# 7_dc_dc_5v_payloads.net
KiCad netlist of a schematic drawn in Altium Designer
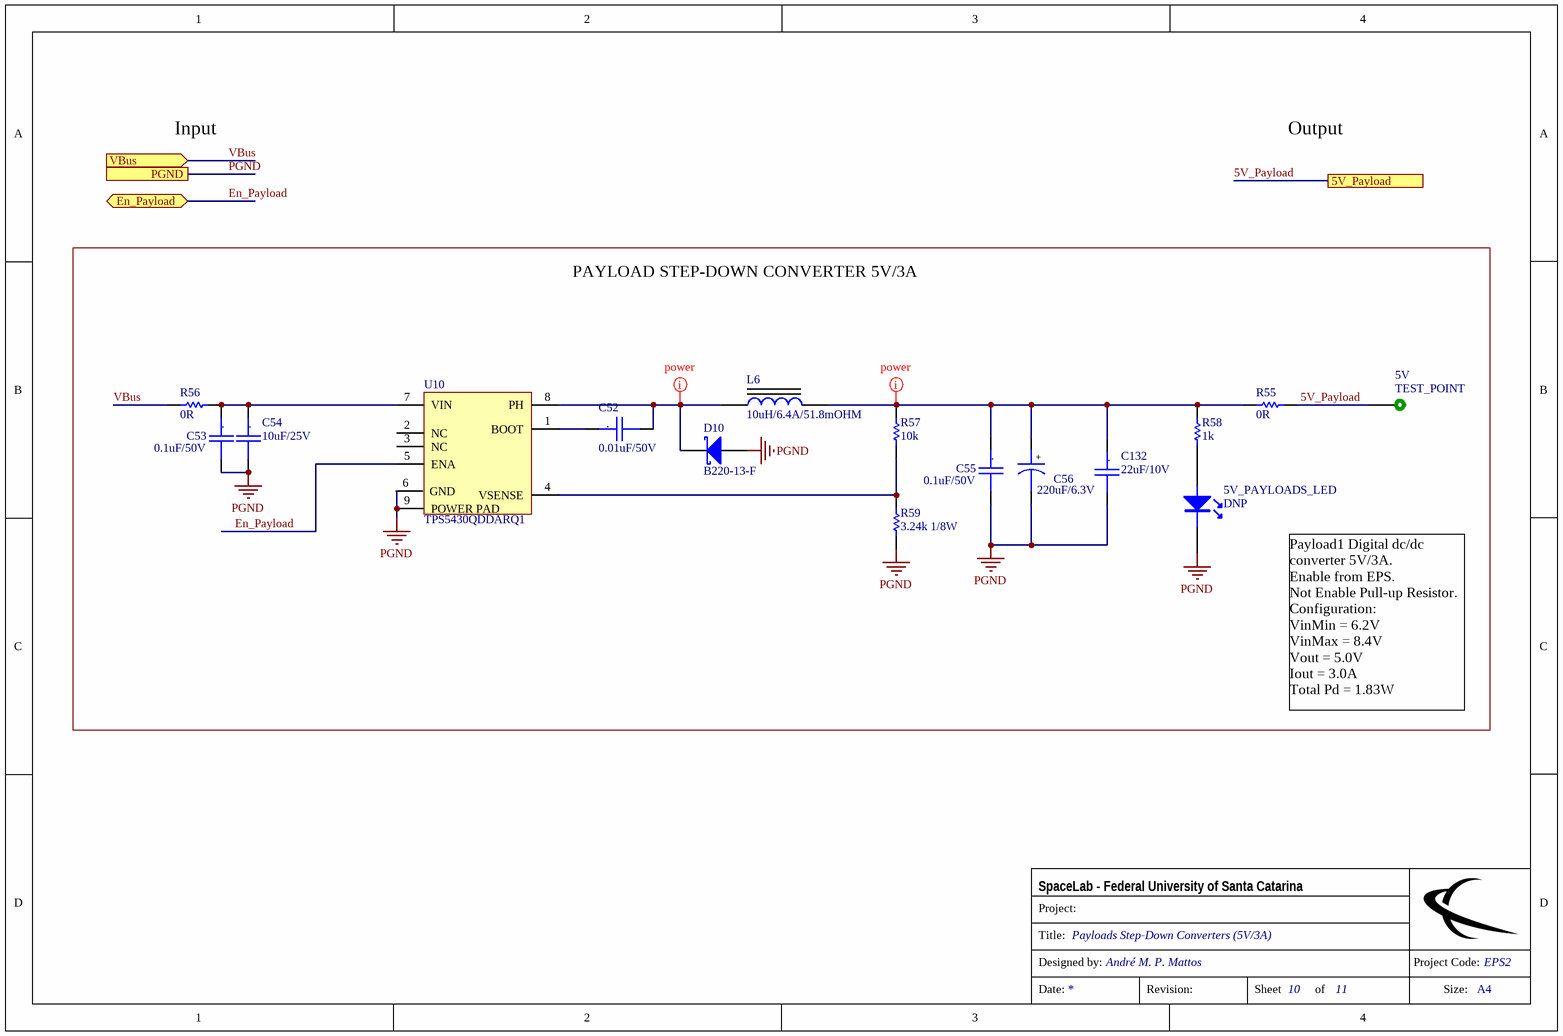
[diagram p0: 7_dc_dc_5v_payloads.schdoc]

(export (version "E")
  (design (tool "Eeschema 10.0.6"))
  (components
    (comp (ref "5V")
      (value "TEST_POINT")
      (footprint "TEST_POINT")
      (description "Test point")
      (libsource (lib "PCB_Project_FlightModel_EPS") (part "TEST_POINT"))
    )
    (comp (ref "5V_PAYLOADS_LED")
      (value "DNP")
      (footprint "0603-LED")
      (description "SMD Green LED")
      (fields (field (name "PARTNUMBER") "150060VS75000") (field (name "MANUFACTURER") "Wurth Electronics"))
      (libsource (lib "PCB_Project_FlightModel_EPS") (part "LED/G_0603"))
    )
    (comp (ref "C52")
      (value "0.01uF/50V")
      (footprint "CC0805")
      (description "CAP CER 0.01uF 50V 10% X7R 0805")
      (fields (field (name "PARTNUMBER") "08055C103KAT4A") (field (name "MANUFACTURER") "Kyocera AVX"))
      (libsource (lib "PCB_Project_FlightModel_EPS") (part "Cap_Cer_X7R_0.01uF_50V_0805"))
    )
    (comp (ref "C53")
      (value "0.1uF/50V")
      (footprint "CC0805")
      (description "CAP CER 0.1UF 50V 10% X7R 0805")
      (fields (field (name "PARTNUMBER") "CC0805KRX7R9BB104") (field (name "MANUFACTURER") "Yageo"))
      (libsource (lib "PCB_Project_FlightModel_EPS") (part "Cap_Cer_X7R_0.1uF_50V_0805"))
    )
    (comp (ref "C54")
      (value "10uF/25V")
      (footprint "CC1206")
      (description "CAP CER 10uF 25V 10% X7R 1206")
      (fields (field (name "PARTNUMBER") "GRM31CR71E106KA12L") (field (name "MANUFACTURER") "Murata"))
      (libsource (lib "PCB_Project_FlightModel_EPS") (part "Cap_Cer_X7R_10uF_25V_1206"))
    )
    (comp (ref "C55")
      (value "0.1uF/50V")
      (footprint "CC0805")
      (description "CAP CER 0.1UF 50V 10% X7R 0805")
      (fields (field (name "PARTNUMBER") "CC0805KRX7R9BB104") (field (name "MANUFACTURER") "Yageo"))
      (libsource (lib "PCB_Project_FlightModel_EPS") (part "Cap_Cer_X7R_0.1uF_50V_0805"))
    )
    (comp (ref "C56")
      (value "220uF/6.3V")
      (footprint "FloripaSatPcbLib:cc1210")
      (description "CAP Tantalum 220uF 6.3V 20% 1210")
      (fields (field (name "PARTNUMBER") "6TPE220MAZB") (field (name "MANUFACTURER") "Panasonic"))
      (libsource (lib "PCB_Project_FlightModel_EPS") (part "Cap_Tant_SMD_220uF_6.3V_1210"))
    )
    (comp (ref "C132")
      (value "22uF/10V")
      (footprint "CC1206")
      (description "CAP CER 22uF 10V 10% X7R 1206")
      (fields (field (name "PARTNUMBER") "GRM31CR71A226KE15L") (field (name "MANUFACTURER") "Murata"))
      (libsource (lib "PCB_Project_FlightModel_EPS") (part "Cap_Cer_X7R_22uF_10V_1206"))
    )
    (comp (ref "D10")
      (value "B220-13-F")
      (footprint "DO-214AA")
      (description "DIODE SCHOTTKY 20V 2A B220-13-F")
      (fields (field (name "MANUFACTURER") "Diodes"))
      (libsource (lib "PCB_Project_FlightModel_EPS") (part "DIODE_SCHOTTKY_20V_2A_MB220-13-F"))
    )
    (comp (ref "L6")
      (value "10uH/6.4A/51.8mOHM")
      (footprint "Ind_IHLP")
      (description "INDUCTOR 2.2UH 6.4A SMD")
      (fields (field (name "PARTNUMBER") "IHLP3232DZER100M11") (field (name "MANUFACTURER") "Vishay Dale"))
      (libsource (lib "PCB_Project_FlightModel_EPS") (part "IND_POWER_10uH_6.4A_51.8mR"))
    )
    (comp (ref "R55")
      (value "0R")
      (footprint "1206")
      (description "RES 0.0 OHM 3/4W JUMP 1206")
      (fields
        (field (name "PARTNUMBER") "HCJ1206ZT0R00")
        (field (name "MANUFACTURER") "Stackpole Electronics")
      )
      (libsource (lib "PCB_Project_FlightModel_EPS") (part "R0R_JUMPER_3/4W_1206"))
    )
    (comp (ref "R56")
      (value "0R")
      (footprint "1206")
      (description "RES 0.0 OHM 3/4W JUMP 1206")
      (fields
        (field (name "PARTNUMBER") "HCJ1206ZT0R00")
        (field (name "MANUFACTURER") "Stackpole Electronics")
      )
      (libsource (lib "PCB_Project_FlightModel_EPS") (part "R0R_JUMPER_3/4W_1206"))
    )
    (comp (ref "R57")
      (value "10k")
      (footprint "0805")
      (description "RES 10K OHM 1/8W 1%  0805")
      (fields (field (name "PARTNUMBER") "CRCW080510K0FKEA") (field (name "MANUFACTURER") "Vishay"))
      (libsource (lib "PCB_Project_FlightModel_EPS") (part "R10k_1%_1/8W_0805"))
    )
    (comp (ref "R58")
      (value "1k")
      (footprint "0603")
      (description "RES 1.0K OHM 1/8W 1% 0603")
      (fields (field (name "PARTNUMBER") "MCT06030C1001FP500") (field (name "MANUFACTURER") "Vishay"))
      (libsource (lib "PCB_Project_FlightModel_EPS") (part "R1.0k_1%_1/8W_0603"))
    )
    (comp (ref "R59")
      (value "3.24k 1/8W")
      (footprint "0805")
      (description "RES 3.24k OHM 1/8W 1% 0805 SMD")
      (fields (field (name "PARTNUMBER") "CRCW08053K24FKEA") (field (name "MANUFACTURER") "Vishay"))
      (libsource (lib "PCB_Project_FlightModel_EPS") (part "R3.24k_1%_1/8W_0805"))
    )
    (comp (ref "U10")
      (value "TPS5430QDDARQ1")
      (footprint "SO8 Power PAD")
      (fields (field (name "MANUFACTURER") "Texas Instruments"))
      (libsource (lib "PCB_Project_FlightModel_EPS") (part "TPS5430QDDARQ1"))
    )
  )
  (nets
    (net (code "1") (name "/5V_Payload") (class "Default")
      (node (ref "5V") (pin "1") (pinfunction "1_1") (pintype "passive"))
      (node (ref "R55") (pin "1") (pinfunction "1_1") (pintype "passive"))
    )
    (net (code "2") (name "/En_Payload") (class "Default")
      (node (ref "U10") (pin "5") (pinfunction "ENA_5") (pintype "passive"))
    )
    (net (code "3") (name "/VBus") (class "Default")
      (node (ref "R56") (pin "2") (pinfunction "2_2") (pintype "passive"))
    )
    (net (code "4") (name "Net-(5V_PAYLOADS_LED-A)") (class "Default")
      (node (ref "5V_PAYLOADS_LED") (pin "1") (pinfunction "A_1") (pintype "passive"))
      (node (ref "R58") (pin "2") (pinfunction "2_2") (pintype "passive"))
    )
    (net (code "5") (name "Net-(C132-Pad1)") (class "Default")
      (node (ref "C132") (pin "1") (pinfunction "1_1") (pintype "passive"))
      (node (ref "C55") (pin "1") (pinfunction "1_1") (pintype "passive"))
      (node (ref "C56") (pin "1") (pinfunction "1_1") (pintype "passive"))
      (node (ref "L6") (pin "2") (pinfunction "2_2") (pintype "passive"))
      (node (ref "R55") (pin "2") (pinfunction "2_2") (pintype "passive"))
      (node (ref "R57") (pin "2") (pinfunction "2_2") (pintype "passive"))
      (node (ref "R58") (pin "1") (pinfunction "1_1") (pintype "passive"))
    )
    (net (code "6") (name "Net-(D10-K)") (class "Default")
      (node (ref "C52") (pin "2") (pinfunction "2_2") (pintype "passive"))
      (node (ref "D10") (pin "1") (pinfunction "K_1") (pintype "passive"))
      (node (ref "L6") (pin "1") (pinfunction "1_1") (pintype "passive"))
      (node (ref "U10") (pin "8") (pinfunction "PH_8") (pintype "passive"))
    )
    (net (code "7") (name "Net-(U10-BOOT)") (class "Default")
      (node (ref "C52") (pin "1") (pinfunction "1_1") (pintype "passive"))
      (node (ref "U10") (pin "1") (pinfunction "BOOT_1") (pintype "passive"))
    )
    (net (code "8") (name "Net-(U10-VIN)") (class "Default")
      (node (ref "C53") (pin "1") (pinfunction "1_1") (pintype "passive"))
      (node (ref "C54") (pin "1") (pinfunction "1_1") (pintype "passive"))
      (node (ref "R56") (pin "1") (pinfunction "1_1") (pintype "passive"))
      (node (ref "U10") (pin "7") (pinfunction "VIN_7") (pintype "passive"))
    )
    (net (code "9") (name "Net-(U10-VSENSE)") (class "Default")
      (node (ref "R57") (pin "1") (pinfunction "1_1") (pintype "passive"))
      (node (ref "R59") (pin "2") (pinfunction "2_2") (pintype "passive"))
      (node (ref "U10") (pin "4") (pinfunction "VSENSE_4") (pintype "passive"))
    )
    (net (code "10") (name "PGND") (class "Default")
      (node (ref "5V_PAYLOADS_LED") (pin "2") (pinfunction "K_2") (pintype "passive"))
      (node (ref "C132") (pin "2") (pinfunction "2_2") (pintype "passive"))
      (node (ref "C53") (pin "2") (pinfunction "2_2") (pintype "passive"))
      (node (ref "C54") (pin "2") (pinfunction "2_2") (pintype "passive"))
      (node (ref "C55") (pin "2") (pinfunction "2_2") (pintype "passive"))
      (node (ref "C56") (pin "2") (pinfunction "2_2") (pintype "passive"))
      (node (ref "D10") (pin "2") (pinfunction "A_2") (pintype "passive"))
      (node (ref "R59") (pin "1") (pinfunction "1_1") (pintype "passive"))
      (node (ref "U10") (pin "6") (pinfunction "GND_6") (pintype "passive"))
      (node (ref "U10") (pin "9") (pinfunction "POWER_PAD_9") (pintype "passive"))
    )
    (net (code "11") (name "unconnected-(U10-NC-Pad2)") (class "Default")
      (node (ref "U10") (pin "2") (pinfunction "NC_2") (pintype "passive"))
    )
    (net (code "12") (name "unconnected-(U10-NC-Pad3)") (class "Default")
      (node (ref "U10") (pin "3") (pinfunction "NC_3") (pintype "passive"))
    )
  )
)
